# current_controller.net
KiCad netlist of a schematic drawn in Altium Designer
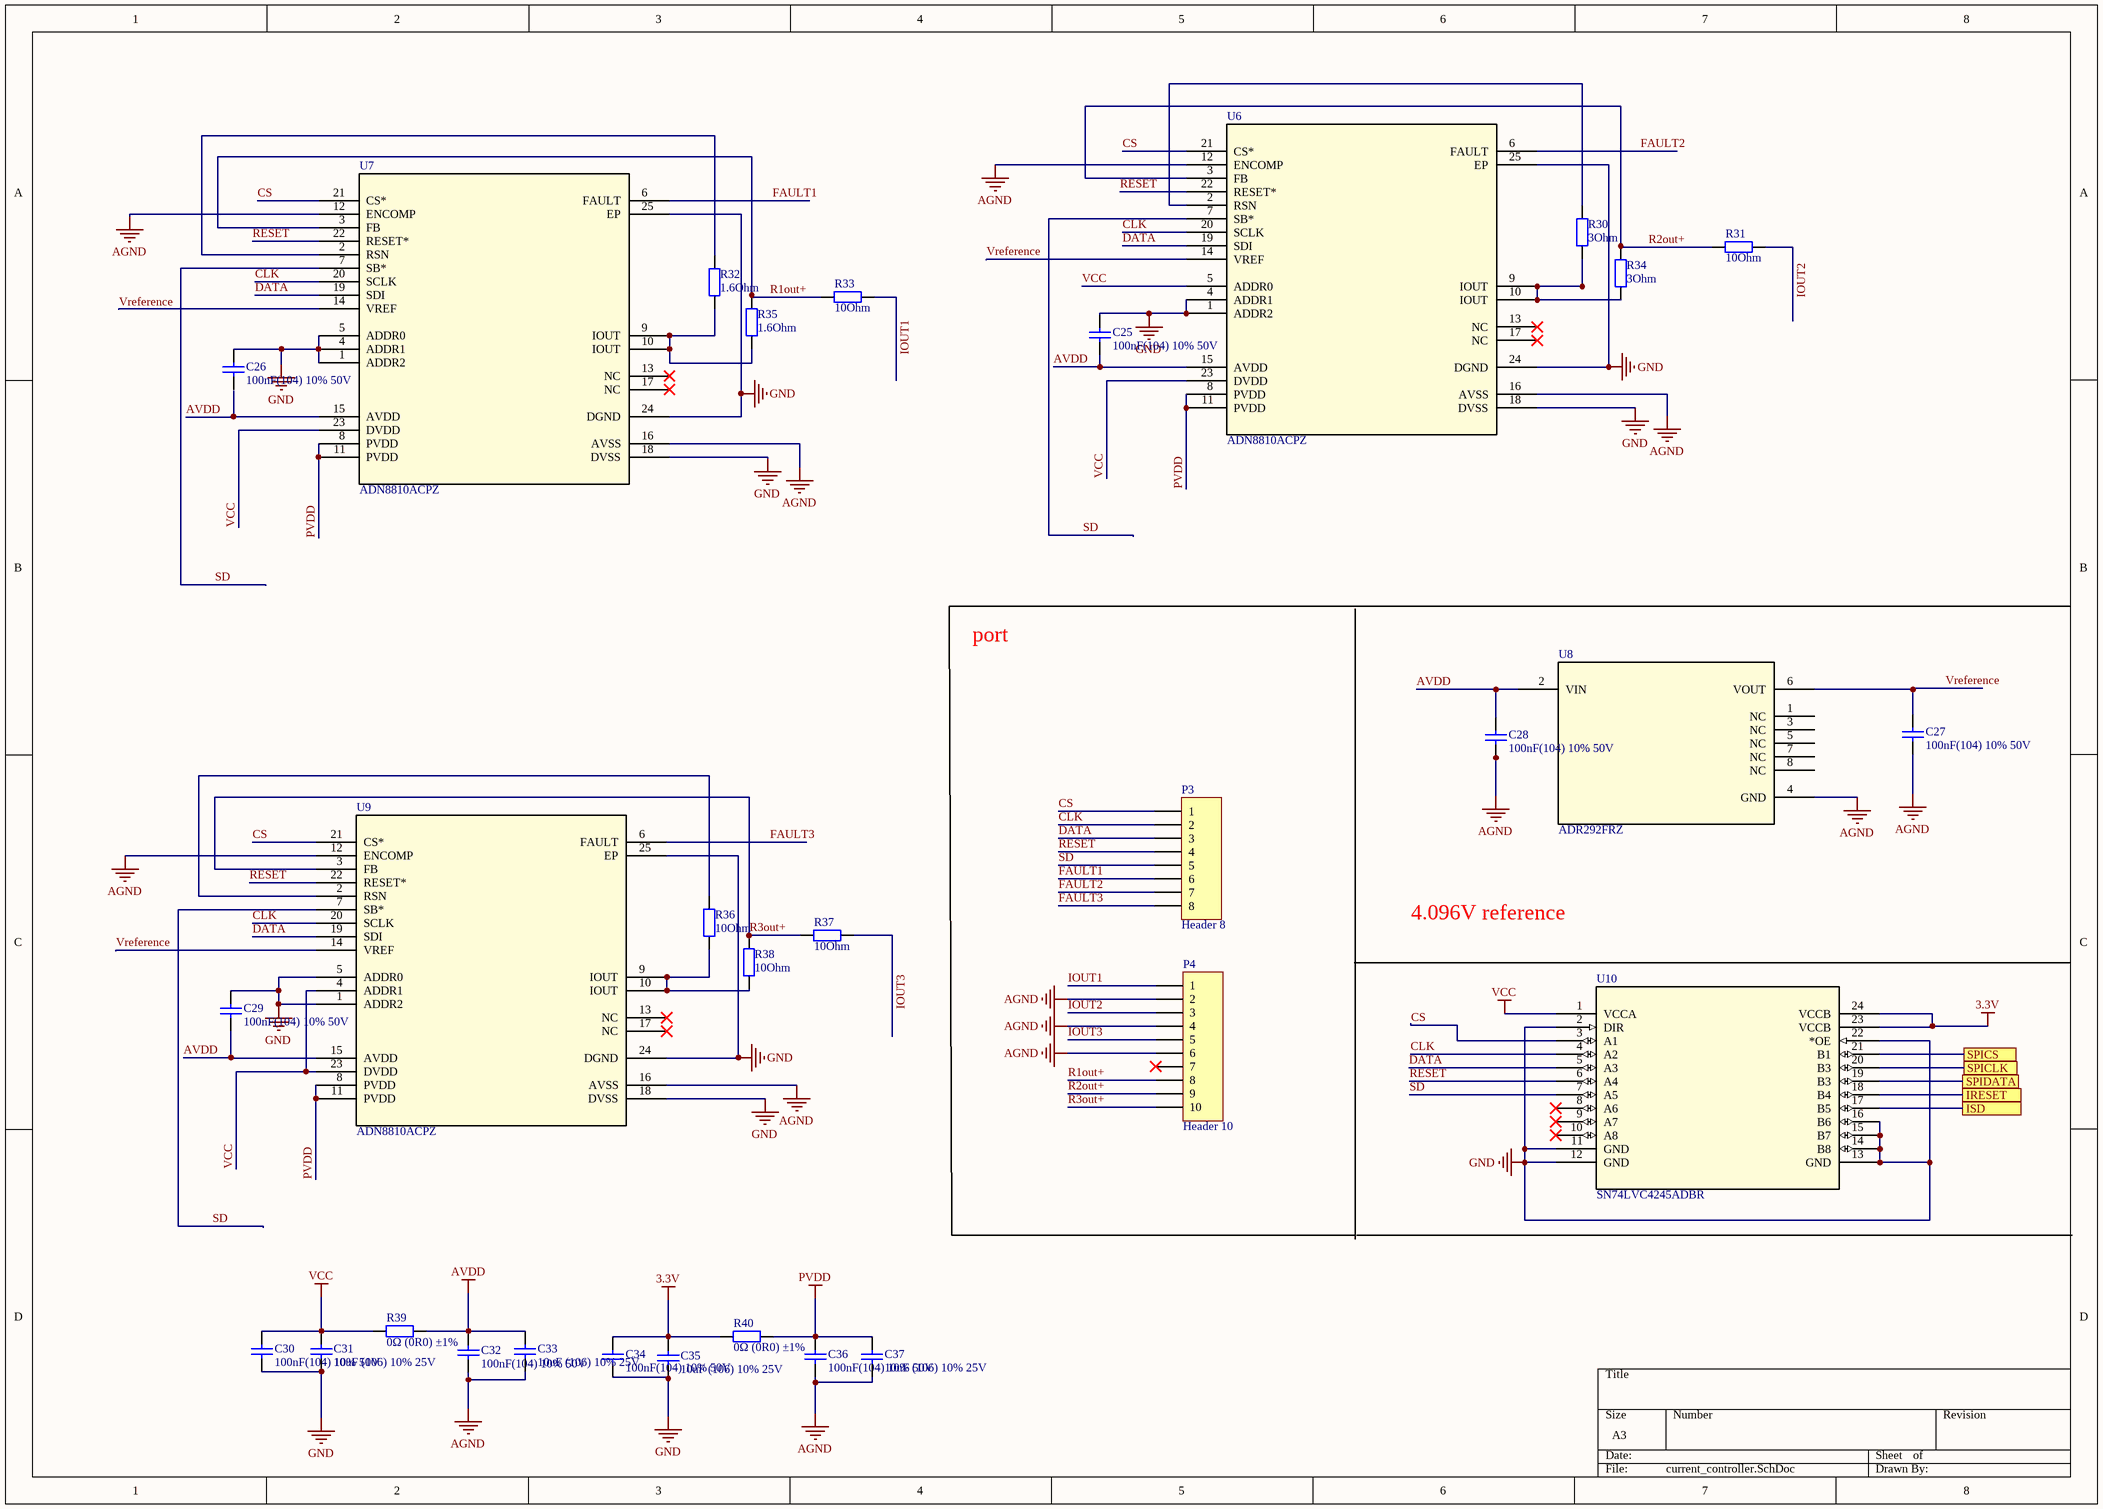
[diagram p0: current_controller.SchDoc]

(export (version "E")
  (design (tool "Eeschema 10.0.6"))
  (components
    (comp (ref "C25")
      (value "100nF(104) 10% 50V")
      (footprint "0805_C")
      (description "贴片电容")
      (libsource (lib "Cap") (part "0805 100nF(104) 10% 50V"))
    )
    (comp (ref "C26")
      (value "100nF(104) 10% 50V")
      (footprint "0805_C")
      (description "贴片电容")
      (libsource (lib "Cap") (part "0805 100nF(104) 10% 50V"))
    )
    (comp (ref "C27")
      (value "100nF(104) 10% 50V")
      (footprint "0805_C")
      (description "贴片电容")
      (libsource (lib "Cap") (part "0805 100nF(104) 10% 50V"))
    )
    (comp (ref "C28")
      (value "100nF(104) 10% 50V")
      (footprint "0805_C")
      (description "贴片电容")
      (libsource (lib "Cap") (part "0805 100nF(104) 10% 50V"))
    )
    (comp (ref "C29")
      (value "100nF(104) 10% 50V")
      (footprint "0805_C")
      (description "贴片电容")
      (libsource (lib "Cap") (part "0805 100nF(104) 10% 50V"))
    )
    (comp (ref "C30")
      (value "100nF(104) 10% 50V")
      (footprint "0805_C")
      (description "贴片电容")
      (libsource (lib "Cap") (part "0805 100nF(104) 10% 50V"))
    )
    (comp (ref "C31")
      (value "10uF (106) 10% 25V")
      (footprint "0805_C")
      (description "贴片电容")
      (libsource (lib "Cap") (part "0805 10uF (106) 10% 25V"))
    )
    (comp (ref "C32")
      (value "100nF(104) 10% 50V")
      (footprint "0805_C")
      (description "贴片电容")
      (libsource (lib "Cap") (part "0805 100nF(104) 10% 50V"))
    )
    (comp (ref "C33")
      (value "10uF (106) 10% 25V")
      (footprint "0805_C")
      (description "贴片电容")
      (libsource (lib "Cap") (part "0805 10uF (106) 10% 25V"))
    )
    (comp (ref "C34")
      (value "100nF(104) 10% 50V")
      (footprint "0805_C")
      (description "贴片电容")
      (libsource (lib "Cap") (part "0805 100nF(104) 10% 50V"))
    )
    (comp (ref "C35")
      (value "10uF (106) 10% 25V")
      (footprint "0805_C")
      (description "贴片电容")
      (libsource (lib "Cap") (part "0805 10uF (106) 10% 25V"))
    )
    (comp (ref "C36")
      (value "100nF(104) 10% 50V")
      (footprint "0805_C")
      (description "贴片电容")
      (libsource (lib "Cap") (part "0805 100nF(104) 10% 50V"))
    )
    (comp (ref "C37")
      (value "10uF (106) 10% 25V")
      (footprint "0805_C")
      (description "贴片电容")
      (libsource (lib "Cap") (part "0805 10uF (106) 10% 25V"))
    )
    (comp (ref "P3")
      (value "Header 8")
      (footprint "HDR1X8")
      (description "Header, 8-Pin")
      (fields (field (name "PUBLISHER") "Altium Limited"))
      (libsource (lib "Miscellaneous Connectors") (part "Header 8"))
    )
    (comp (ref "P4")
      (value "Header 10")
      (footprint "HDR1X10")
      (description "Header, 10-Pin")
      (fields (field (name "PUBLISHER") "Altium Limited"))
      (libsource (lib "Miscellaneous Connectors") (part "Header 10"))
    )
    (comp (ref "R30")
      (value "3Ohm")
      (footprint "AXIAL-0.4")
      (description "1% resistance")
      (fields (field (name "PUBLISHER") "Altium Limited"))
      (libsource (lib "Miscellaneous Devices") (part "Res2"))
    )
    (comp (ref "R31")
      (value "10Ohm")
      (footprint "AXIAL-0.4")
      (description "1% resistance")
      (fields (field (name "PUBLISHER") "Altium Limited"))
      (libsource (lib "") (part "Res2_1"))
    )
    (comp (ref "R32")
      (value "1.6Ohm")
      (footprint "AXIAL-0.4")
      (description "1% resistance")
      (fields (field (name "PUBLISHER") "Altium Limited"))
      (libsource (lib "Miscellaneous Devices") (part "Res2"))
    )
    (comp (ref "R33")
      (value "10Ohm")
      (footprint "AXIAL-0.4")
      (description "1% resistance")
      (fields (field (name "PUBLISHER") "Altium Limited"))
      (libsource (lib "") (part "Res2_1"))
    )
    (comp (ref "R34")
      (value "3Ohm")
      (footprint "AXIAL-0.4")
      (description "1% resistance")
      (fields (field (name "PUBLISHER") "Altium Limited"))
      (libsource (lib "Miscellaneous Devices") (part "Res2"))
    )
    (comp (ref "R35")
      (value "1.6Ohm")
      (footprint "AXIAL-0.4")
      (description "1% resistance")
      (fields (field (name "PUBLISHER") "Altium Limited"))
      (libsource (lib "Miscellaneous Devices") (part "Res2"))
    )
    (comp (ref "R36")
      (value "10Ohm")
      (footprint "AXIAL-0.4")
      (description "1% resistance")
      (fields (field (name "PUBLISHER") "Altium Limited"))
      (libsource (lib "Miscellaneous Devices") (part "Res2"))
    )
    (comp (ref "R37")
      (value "10Ohm")
      (footprint "AXIAL-0.4")
      (description "1% resistance")
      (fields (field (name "PUBLISHER") "Altium Limited"))
      (libsource (lib "") (part "Res2_1"))
    )
    (comp (ref "R38")
      (value "10Ohm")
      (footprint "AXIAL-0.4")
      (description "1% resistance")
      (fields (field (name "PUBLISHER") "Altium Limited"))
      (libsource (lib "Miscellaneous Devices") (part "Res2"))
    )
    (comp (ref "R39")
      (value "0Ω (0R0) ±1%")
      (footprint "0603_R")
      (description "贴片电阻")
      (libsource (lib "RES") (part "0603 0Ω (0R0) 1%"))
    )
    (comp (ref "R40")
      (value "0Ω (0R0) ±1%")
      (footprint "0603_R")
      (description "贴片电阻")
      (libsource (lib "RES") (part "0603 0Ω (0R0) 1%"))
    )
    (comp (ref "U6")
      (value "ADN8810ACPZ")
      (footprint "CP_24_1")
      (description "Imported")
      (libsource (lib "ADN8810") (part "ADN8810ACPZ"))
    )
    (comp (ref "U7")
      (value "ADN8810ACPZ")
      (footprint "CP_24_1")
      (description "Imported")
      (libsource (lib "ADN8810") (part "ADN8810ACPZ"))
    )
    (comp (ref "U8")
      (value "ADR292FRZ")
      (footprint "R_8")
      (description "Imported")
      (libsource (lib "ADR292") (part "ADR292FRZ"))
    )
    (comp (ref "U9")
      (value "ADN8810ACPZ")
      (footprint "CP_24_1")
      (description "Imported")
      (libsource (lib "ADN8810") (part "ADN8810ACPZ"))
    )
    (comp (ref "U10")
      (value "SN74LVC4245ADBR")
      (footprint "DB24")
      (description "Octal Bus Transceiver And 3.3-V To 5-V Shifter With 3-State Outputs")
      (fields
        (field (name "MANUFACTURER") "Texas Instruments")
        (field (name "GENERIC_PART_NUMBER") "SN74LVC4245A")
        (field (name "COPYRIGHT") "Copyright (C) 2018 Accelerated Designs. All rights reserved")
      )
      (libsource (lib "SN74LVC4245ADBR") (part "SN74LVC4245ADBR"))
    )
  )
  (nets
    (net (code "1") (name "/CLK") (class "Default")
      (node (ref "P3") (pin "2") (pinfunction "2_2") (pintype "passive"))
      (node (ref "U10") (pin "4") (pinfunction "A2_4") (pintype "bidirectional"))
      (node (ref "U6") (pin "20") (pinfunction "SCLK_20") (pintype "passive"))
      (node (ref "U7") (pin "20") (pinfunction "SCLK_20") (pintype "passive"))
      (node (ref "U9") (pin "20") (pinfunction "SCLK_20") (pintype "passive"))
    )
    (net (code "2") (name "/CS") (class "Default")
      (node (ref "P3") (pin "1") (pinfunction "1_1") (pintype "passive"))
      (node (ref "U10") (pin "3") (pinfunction "A1_3") (pintype "bidirectional"))
      (node (ref "U6") (pin "21") (pinfunction "CS*_21") (pintype "passive"))
      (node (ref "U7") (pin "21") (pinfunction "CS*_21") (pintype "passive"))
      (node (ref "U9") (pin "21") (pinfunction "CS*_21") (pintype "passive"))
    )
    (net (code "3") (name "/DATA") (class "Default")
      (node (ref "P3") (pin "3") (pinfunction "3_3") (pintype "passive"))
      (node (ref "U10") (pin "5") (pinfunction "A3_5") (pintype "bidirectional"))
      (node (ref "U6") (pin "19") (pinfunction "SDI_19") (pintype "passive"))
      (node (ref "U7") (pin "19") (pinfunction "SDI_19") (pintype "passive"))
      (node (ref "U9") (pin "19") (pinfunction "SDI_19") (pintype "passive"))
    )
    (net (code "4") (name "/FAULT1") (class "Default")
      (node (ref "P3") (pin "6") (pinfunction "6_6") (pintype "passive"))
      (node (ref "U7") (pin "6") (pinfunction "FAULT_6") (pintype "passive"))
    )
    (net (code "5") (name "/FAULT2") (class "Default")
      (node (ref "P3") (pin "7") (pinfunction "7_7") (pintype "passive"))
      (node (ref "U6") (pin "6") (pinfunction "FAULT_6") (pintype "passive"))
    )
    (net (code "6") (name "/FAULT3") (class "Default")
      (node (ref "P3") (pin "8") (pinfunction "8_8") (pintype "passive"))
      (node (ref "U9") (pin "6") (pinfunction "FAULT_6") (pintype "passive"))
    )
    (net (code "7") (name "/IOUT1") (class "Default")
      (node (ref "P4") (pin "1") (pinfunction "1_1") (pintype "passive"))
      (node (ref "R33") (pin "1") (pinfunction "1_1") (pintype "passive"))
    )
    (net (code "8") (name "/IOUT2") (class "Default")
      (node (ref "P4") (pin "3") (pinfunction "3_3") (pintype "passive"))
      (node (ref "R31") (pin "1") (pinfunction "1_1") (pintype "passive"))
    )
    (net (code "9") (name "/IOUT3") (class "Default")
      (node (ref "P4") (pin "5") (pinfunction "5_5") (pintype "passive"))
      (node (ref "R37") (pin "1") (pinfunction "1_1") (pintype "passive"))
    )
    (net (code "10") (name "/IRESET") (class "Default")
      (node (ref "U10") (pin "18") (pinfunction "B4_18") (pintype "bidirectional"))
    )
    (net (code "11") (name "/ISD") (class "Default")
      (node (ref "U10") (pin "17") (pinfunction "B5_17") (pintype "bidirectional"))
    )
    (net (code "12") (name "/R1out+") (class "Default")
      (node (ref "P4") (pin "8") (pinfunction "8_8") (pintype "passive"))
      (node (ref "R33") (pin "2") (pinfunction "2_2") (pintype "passive"))
      (node (ref "R35") (pin "2") (pinfunction "2_2") (pintype "passive"))
      (node (ref "U7") (pin "3") (pinfunction "FB_3") (pintype "passive"))
    )
    (net (code "13") (name "/R2out+") (class "Default")
      (node (ref "P4") (pin "9") (pinfunction "9_9") (pintype "passive"))
      (node (ref "R31") (pin "2") (pinfunction "2_2") (pintype "passive"))
      (node (ref "R34") (pin "2") (pinfunction "2_2") (pintype "passive"))
      (node (ref "U6") (pin "3") (pinfunction "FB_3") (pintype "passive"))
    )
    (net (code "14") (name "/R3out+") (class "Default")
      (node (ref "P4") (pin "10") (pinfunction "10_10") (pintype "passive"))
      (node (ref "R37") (pin "2") (pinfunction "2_2") (pintype "passive"))
      (node (ref "R38") (pin "2") (pinfunction "2_2") (pintype "passive"))
      (node (ref "U9") (pin "3") (pinfunction "FB_3") (pintype "passive"))
    )
    (net (code "15") (name "/RESET") (class "Default")
      (node (ref "P3") (pin "4") (pinfunction "4_4") (pintype "passive"))
      (node (ref "U10") (pin "6") (pinfunction "A4_6") (pintype "bidirectional"))
      (node (ref "U6") (pin "22") (pinfunction "RESET*_22") (pintype "passive"))
      (node (ref "U7") (pin "22") (pinfunction "RESET*_22") (pintype "passive"))
      (node (ref "U9") (pin "22") (pinfunction "RESET*_22") (pintype "passive"))
    )
    (net (code "16") (name "/SD") (class "Default")
      (node (ref "P3") (pin "5") (pinfunction "5_5") (pintype "passive"))
      (node (ref "U10") (pin "7") (pinfunction "A5_7") (pintype "bidirectional"))
      (node (ref "U6") (pin "7") (pinfunction "SB*_7") (pintype "passive"))
      (node (ref "U7") (pin "7") (pinfunction "SB*_7") (pintype "passive"))
      (node (ref "U9") (pin "7") (pinfunction "SB*_7") (pintype "passive"))
    )
    (net (code "17") (name "/SPICLK") (class "Default")
      (node (ref "U10") (pin "20") (pinfunction "B3_20") (pintype "bidirectional"))
    )
    (net (code "18") (name "/SPICS") (class "Default")
      (node (ref "U10") (pin "21") (pinfunction "B1_21") (pintype "bidirectional"))
    )
    (net (code "19") (name "/SPIDATA") (class "Default")
      (node (ref "U10") (pin "19") (pinfunction "B3_19") (pintype "bidirectional"))
    )
    (net (code "20") (name "/Vreference") (class "Default")
      (node (ref "C27") (pin "2") (pinfunction "2_2") (pintype "passive"))
      (node (ref "U6") (pin "14") (pinfunction "VREF_14") (pintype "passive"))
      (node (ref "U7") (pin "14") (pinfunction "VREF_14") (pintype "passive"))
      (node (ref "U8") (pin "6") (pinfunction "VOUT_6") (pintype "passive"))
      (node (ref "U9") (pin "14") (pinfunction "VREF_14") (pintype "passive"))
    )
    (net (code "21") (name "3.3V") (class "Default")
      (node (ref "C34") (pin "2") (pinfunction "2_2") (pintype "passive"))
      (node (ref "R40") (pin "1") (pinfunction "1_1") (pintype "passive"))
      (node (ref "U10") (pin "23") (pinfunction "VCCB_23") (pintype "power_in"))
      (node (ref "U10") (pin "24") (pinfunction "VCCB_24") (pintype "power_in"))
    )
    (net (code "22") (name "AGND") (class "Default")
      (node (ref "C27") (pin "1") (pinfunction "1_1") (pintype "passive"))
      (node (ref "C28") (pin "1") (pinfunction "1_1") (pintype "passive"))
      (node (ref "C32") (pin "2") (pinfunction "2_2") (pintype "passive"))
      (node (ref "C33") (pin "2") (pinfunction "2_2") (pintype "passive"))
      (node (ref "C36") (pin "2") (pinfunction "2_2") (pintype "passive"))
      (node (ref "C37") (pin "2") (pinfunction "2_2") (pintype "passive"))
      (node (ref "P4") (pin "2") (pinfunction "2_2") (pintype "passive"))
      (node (ref "P4") (pin "4") (pinfunction "4_4") (pintype "passive"))
      (node (ref "P4") (pin "6") (pinfunction "6_6") (pintype "passive"))
      (node (ref "U6") (pin "12") (pinfunction "ENCOMP_12") (pintype "passive"))
      (node (ref "U6") (pin "16") (pinfunction "AVSS_16") (pintype "passive"))
      (node (ref "U7") (pin "12") (pinfunction "ENCOMP_12") (pintype "passive"))
      (node (ref "U7") (pin "16") (pinfunction "AVSS_16") (pintype "passive"))
      (node (ref "U8") (pin "4") (pinfunction "GND_4") (pintype "passive"))
      (node (ref "U9") (pin "12") (pinfunction "ENCOMP_12") (pintype "passive"))
      (node (ref "U9") (pin "16") (pinfunction "AVSS_16") (pintype "passive"))
    )
    (net (code "23") (name "AVDD") (class "Default")
      (node (ref "C25") (pin "1") (pinfunction "1_1") (pintype "passive"))
      (node (ref "C28") (pin "2") (pinfunction "2_2") (pintype "passive"))
      (node (ref "C29") (pin "1") (pinfunction "1_1") (pintype "passive"))
      (node (ref "C33") (pin "1") (pinfunction "1_1") (pintype "passive"))
      (node (ref "R39") (pin "2") (pinfunction "2_2") (pintype "passive"))
      (node (ref "U6") (pin "15") (pinfunction "AVDD_15") (pintype "power_in"))
      (node (ref "U7") (pin "15") (pinfunction "AVDD_15") (pintype "power_in"))
      (node (ref "U8") (pin "2") (pinfunction "VIN_2") (pintype "passive"))
      (node (ref "U9") (pin "15") (pinfunction "AVDD_15") (pintype "power_in"))
    )
    (net (code "24") (name "GND") (class "Default")
      (node (ref "C25") (pin "2") (pinfunction "2_2") (pintype "passive"))
      (node (ref "C26") (pin "2") (pinfunction "2_2") (pintype "passive"))
      (node (ref "C29") (pin "2") (pinfunction "2_2") (pintype "passive"))
      (node (ref "C30") (pin "2") (pinfunction "2_2") (pintype "passive"))
      (node (ref "C31") (pin "1") (pinfunction "1_1") (pintype "passive"))
      (node (ref "C34") (pin "1") (pinfunction "1_1") (pintype "passive"))
      (node (ref "C35") (pin "1") (pinfunction "1_1") (pintype "passive"))
      (node (ref "U10") (pin "11") (pinfunction "GND_11") (pintype "power_in"))
      (node (ref "U10") (pin "12") (pinfunction "GND_12") (pintype "power_in"))
      (node (ref "U10") (pin "13") (pinfunction "GND_13") (pintype "power_in"))
      (node (ref "U10") (pin "14") (pinfunction "B8_14") (pintype "bidirectional"))
      (node (ref "U10") (pin "15") (pinfunction "B7_15") (pintype "bidirectional"))
      (node (ref "U10") (pin "16") (pinfunction "B6_16") (pintype "bidirectional"))
      (node (ref "U10") (pin "2") (pinfunction "DIR_2") (pintype "input"))
      (node (ref "U10") (pin "22") (pinfunction "*OE_22") (pintype "input"))
      (node (ref "U6") (pin "1") (pinfunction "ADDR2_1") (pintype "passive"))
      (node (ref "U6") (pin "18") (pinfunction "DVSS_18") (pintype "passive"))
      (node (ref "U6") (pin "24") (pinfunction "DGND_24") (pintype "passive"))
      (node (ref "U6") (pin "25") (pinfunction "EP_25") (pintype "passive"))
      (node (ref "U6") (pin "4") (pinfunction "ADDR1_4") (pintype "passive"))
      (node (ref "U7") (pin "1") (pinfunction "ADDR2_1") (pintype "passive"))
      (node (ref "U7") (pin "18") (pinfunction "DVSS_18") (pintype "passive"))
      (node (ref "U7") (pin "24") (pinfunction "DGND_24") (pintype "passive"))
      (node (ref "U7") (pin "25") (pinfunction "EP_25") (pintype "passive"))
      (node (ref "U7") (pin "4") (pinfunction "ADDR1_4") (pintype "passive"))
      (node (ref "U7") (pin "5") (pinfunction "ADDR0_5") (pintype "passive"))
      (node (ref "U9") (pin "1") (pinfunction "ADDR2_1") (pintype "passive"))
      (node (ref "U9") (pin "18") (pinfunction "DVSS_18") (pintype "passive"))
      (node (ref "U9") (pin "24") (pinfunction "DGND_24") (pintype "passive"))
      (node (ref "U9") (pin "25") (pinfunction "EP_25") (pintype "passive"))
      (node (ref "U9") (pin "5") (pinfunction "ADDR0_5") (pintype "passive"))
    )
    (net (code "25") (name "Net-(R30-Pad1)") (class "Default")
      (node (ref "R30") (pin "1") (pinfunction "1_1") (pintype "passive"))
      (node (ref "R34") (pin "1") (pinfunction "1_1") (pintype "passive"))
      (node (ref "U6") (pin "10") (pinfunction "IOUT_10") (pintype "passive"))
      (node (ref "U6") (pin "9") (pinfunction "IOUT_9") (pintype "passive"))
    )
    (net (code "26") (name "Net-(R32-Pad1)") (class "Default")
      (node (ref "R32") (pin "1") (pinfunction "1_1") (pintype "passive"))
      (node (ref "R35") (pin "1") (pinfunction "1_1") (pintype "passive"))
      (node (ref "U7") (pin "10") (pinfunction "IOUT_10") (pintype "passive"))
      (node (ref "U7") (pin "9") (pinfunction "IOUT_9") (pintype "passive"))
    )
    (net (code "27") (name "Net-(R36-Pad1)") (class "Default")
      (node (ref "R36") (pin "1") (pinfunction "1_1") (pintype "passive"))
      (node (ref "R38") (pin "1") (pinfunction "1_1") (pintype "passive"))
      (node (ref "U9") (pin "10") (pinfunction "IOUT_10") (pintype "passive"))
      (node (ref "U9") (pin "9") (pinfunction "IOUT_9") (pintype "passive"))
    )
    (net (code "28") (name "Net-(U6-RSN)") (class "Default")
      (node (ref "R30") (pin "2") (pinfunction "2_2") (pintype "passive"))
      (node (ref "U6") (pin "2") (pinfunction "RSN_2") (pintype "passive"))
    )
    (net (code "29") (name "Net-(U7-RSN)") (class "Default")
      (node (ref "R32") (pin "2") (pinfunction "2_2") (pintype "passive"))
      (node (ref "U7") (pin "2") (pinfunction "RSN_2") (pintype "passive"))
    )
    (net (code "30") (name "Net-(U9-RSN)") (class "Default")
      (node (ref "R36") (pin "2") (pinfunction "2_2") (pintype "passive"))
      (node (ref "U9") (pin "2") (pinfunction "RSN_2") (pintype "passive"))
    )
    (net (code "31") (name "PVDD") (class "Default")
      (node (ref "C36") (pin "1") (pinfunction "1_1") (pintype "passive"))
      (node (ref "C37") (pin "1") (pinfunction "1_1") (pintype "passive"))
      (node (ref "R40") (pin "2") (pinfunction "2_2") (pintype "passive"))
      (node (ref "U6") (pin "11") (pinfunction "PVDD_11") (pintype "power_in"))
      (node (ref "U6") (pin "8") (pinfunction "PVDD_8") (pintype "power_in"))
      (node (ref "U7") (pin "11") (pinfunction "PVDD_11") (pintype "power_in"))
      (node (ref "U7") (pin "8") (pinfunction "PVDD_8") (pintype "power_in"))
      (node (ref "U9") (pin "11") (pinfunction "PVDD_11") (pintype "power_in"))
      (node (ref "U9") (pin "8") (pinfunction "PVDD_8") (pintype "power_in"))
    )
    (net (code "32") (name "VCC") (class "Default")
      (node (ref "C30") (pin "1") (pinfunction "1_1") (pintype "passive"))
      (node (ref "C31") (pin "2") (pinfunction "2_2") (pintype "passive"))
      (node (ref "R39") (pin "1") (pinfunction "1_1") (pintype "passive"))
      (node (ref "U10") (pin "1") (pinfunction "VCCA_1") (pintype "power_in"))
      (node (ref "U6") (pin "23") (pinfunction "DVDD_23") (pintype "power_in"))
      (node (ref "U6") (pin "5") (pinfunction "ADDR0_5") (pintype "passive"))
      (node (ref "U7") (pin "23") (pinfunction "DVDD_23") (pintype "power_in"))
      (node (ref "U9") (pin "23") (pinfunction "DVDD_23") (pintype "power_in"))
      (node (ref "U9") (pin "4") (pinfunction "ADDR1_4") (pintype "passive"))
    )
    (net (code "33") (name "unconnected-(C26-Pad1)") (class "Default")
      (node (ref "C26") (pin "1") (pinfunction "1_1") (pintype "passive"))
    )
    (net (code "34") (name "unconnected-(C32-Pad1)") (class "Default")
      (node (ref "C32") (pin "1") (pinfunction "1_1") (pintype "passive"))
    )
    (net (code "35") (name "unconnected-(C35-Pad2)") (class "Default")
      (node (ref "C35") (pin "2") (pinfunction "2_2") (pintype "passive"))
    )
    (net (code "36") (name "unconnected-(P4-Pad7)") (class "Default")
      (node (ref "P4") (pin "7") (pinfunction "7_7") (pintype "passive+no_connect"))
    )
    (net (code "37") (name "unconnected-(U6-NC-Pad13)") (class "Default")
      (node (ref "U6") (pin "13") (pinfunction "NC_13") (pintype "passive+no_connect"))
    )
    (net (code "38") (name "unconnected-(U6-NC-Pad17)") (class "Default")
      (node (ref "U6") (pin "17") (pinfunction "NC_17") (pintype "passive+no_connect"))
    )
    (net (code "39") (name "unconnected-(U7-NC-Pad13)") (class "Default")
      (node (ref "U7") (pin "13") (pinfunction "NC_13") (pintype "passive+no_connect"))
    )
    (net (code "40") (name "unconnected-(U7-NC-Pad17)") (class "Default")
      (node (ref "U7") (pin "17") (pinfunction "NC_17") (pintype "passive+no_connect"))
    )
    (net (code "41") (name "unconnected-(U8-NC-Pad1)") (class "Default")
      (node (ref "U8") (pin "1") (pinfunction "NC_1") (pintype "passive"))
    )
    (net (code "42") (name "unconnected-(U8-NC-Pad3)") (class "Default")
      (node (ref "U8") (pin "3") (pinfunction "NC_3") (pintype "passive"))
    )
    (net (code "43") (name "unconnected-(U8-NC-Pad5)") (class "Default")
      (node (ref "U8") (pin "5") (pinfunction "NC_5") (pintype "passive"))
    )
    (net (code "44") (name "unconnected-(U8-NC-Pad7)") (class "Default")
      (node (ref "U8") (pin "7") (pinfunction "NC_7") (pintype "passive"))
    )
    (net (code "45") (name "unconnected-(U8-NC-Pad8)") (class "Default")
      (node (ref "U8") (pin "8") (pinfunction "NC_8") (pintype "passive"))
    )
    (net (code "46") (name "unconnected-(U9-NC-Pad13)") (class "Default")
      (node (ref "U9") (pin "13") (pinfunction "NC_13") (pintype "passive+no_connect"))
    )
    (net (code "47") (name "unconnected-(U9-NC-Pad17)") (class "Default")
      (node (ref "U9") (pin "17") (pinfunction "NC_17") (pintype "passive+no_connect"))
    )
    (net (code "48") (name "unconnected-(U10-A6-Pad8)") (class "Default")
      (node (ref "U10") (pin "8") (pinfunction "A6_8") (pintype "bidirectional+no_connect"))
    )
    (net (code "49") (name "unconnected-(U10-A7-Pad9)") (class "Default")
      (node (ref "U10") (pin "9") (pinfunction "A7_9") (pintype "bidirectional+no_connect"))
    )
    (net (code "50") (name "unconnected-(U10-A8-Pad10)") (class "Default")
      (node (ref "U10") (pin "10") (pinfunction "A8_10") (pintype "bidirectional+no_connect"))
    )
  )
)
